# D1_Breakout_-_LCD_TH_Dupont_RJ45_Logo.net
KiCad netlist of a schematic drawn in EAGLE
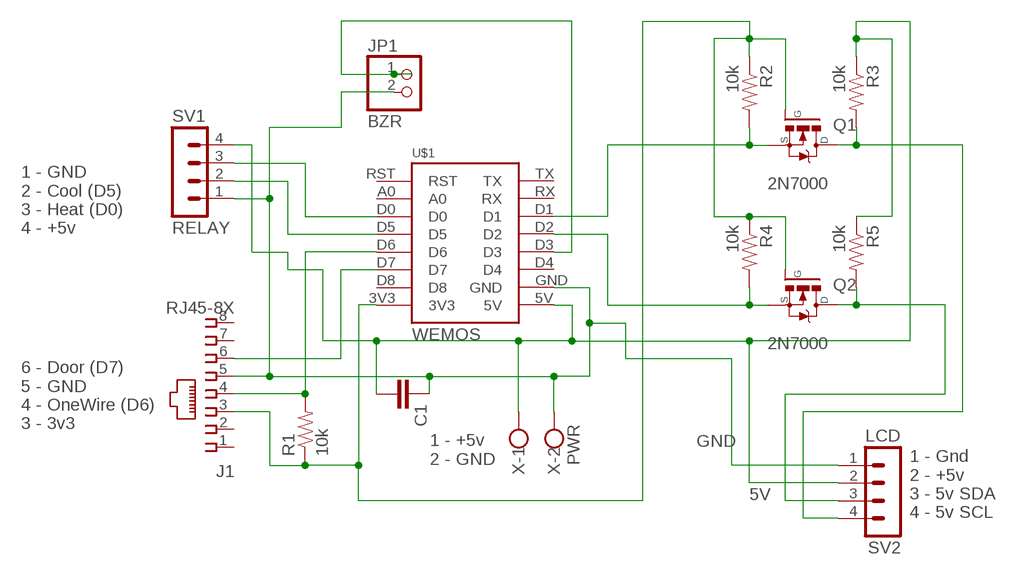
[diagram p0: schematic, sheet 1]

(export (version "E")
  (design (tool "Eeschema 10.0.6"))
  (components
    (comp (ref "C1")
      (value "100uF")
      (footprint "eagle-import:C5B3")
      (libsource (lib "eagle-import") (part "C5/3"))
    )
    (comp (ref "J1")
      (value "RJ45-8X")
      (footprint "eagle-import:RJ45-NO-SHIELD-NOLINE")
      (libsource (lib "eagle-import") (part "RJ45-8X"))
    )
    (comp (ref "JP1")
      (value "BZR")
      (footprint "eagle-import:1X02")
      (libsource (lib "eagle-import") (part "PINHD-1X2"))
    )
    (comp (ref "Q1")
      (value "2N7000")
      (footprint "eagle-import:TO-92")
      (libsource (lib "eagle-import") (part "2N7000"))
    )
    (comp (ref "Q2")
      (value "2N7000")
      (footprint "eagle-import:TO-92")
      (libsource (lib "eagle-import") (part "2N7000"))
    )
    (comp (ref "R1")
      (value "10k")
      (footprint "eagle-import:AXIAL-0.3")
      (libsource (lib "eagle-import") (part "10KOHM-HORIZ-1/4W-1%"))
    )
    (comp (ref "R2")
      (value "10k")
      (footprint "eagle-import:AXIAL-0.3")
      (libsource (lib "eagle-import") (part "10KOHM-HORIZ-1/4W-1%"))
    )
    (comp (ref "R3")
      (value "10k")
      (footprint "eagle-import:AXIAL-0.3")
      (libsource (lib "eagle-import") (part "10KOHM-HORIZ-1/4W-1%"))
    )
    (comp (ref "R4")
      (value "10k")
      (footprint "eagle-import:AXIAL-0.3")
      (libsource (lib "eagle-import") (part "10KOHM-HORIZ-1/4W-1%"))
    )
    (comp (ref "R5")
      (value "10k")
      (footprint "eagle-import:AXIAL-0.3")
      (libsource (lib "eagle-import") (part "10KOHM-HORIZ-1/4W-1%"))
    )
    (comp (ref "SV1")
      (value "RELAY")
      (footprint "eagle-import:MA04-1")
      (libsource (lib "eagle-import") (part "MA04-1"))
    )
    (comp (ref "SV2")
      (value "LCD")
      (footprint "eagle-import:MA04-1")
      (libsource (lib "eagle-import") (part "MA04-1"))
    )
    (comp (ref "U$1")
      (value "WEMOS")
      (footprint "eagle-import:WEMOS")
      (libsource (lib "eagle-import") (part "WEMOS"))
    )
    (comp (ref "X")
      (value "PWR")
      (footprint "eagle-import:W237-102")
      (fields (field (name "MPN") "237-102"))
      (libsource (lib "eagle-import") (part "W237-102"))
    )
  )
  (nets
    (net (code "1") (name "/5V") (class "Default")
      (node (ref "C1") (pin "2") (pinfunction "2_2") (pintype "passive"))
      (node (ref "R3") (pin "P$1") (pinfunction "1_P$1") (pintype "passive"))
      (node (ref "R5") (pin "P$1") (pinfunction "1_P$1") (pintype "passive"))
      (node (ref "SV1") (pin "4") (pinfunction "4_4") (pintype "passive"))
      (node (ref "SV2") (pin "2") (pinfunction "2_2") (pintype "passive"))
      (node (ref "U$1") (pin "5V") (pinfunction "5V_5V") (pintype "bidirectional"))
      (node (ref "X") (pin "1") (pinfunction "KL_1") (pintype "passive"))
    )
    (net (code "2") (name "/GND") (class "Default")
      (node (ref "C1") (pin "1") (pinfunction "1_1") (pintype "passive"))
      (node (ref "J1") (pin "5") (pinfunction "5_5") (pintype "passive"))
      (node (ref "JP1") (pin "2") (pinfunction "2_2") (pintype "passive"))
      (node (ref "SV1") (pin "1") (pinfunction "1_1") (pintype "passive"))
      (node (ref "SV2") (pin "1") (pinfunction "1_1") (pintype "passive"))
      (node (ref "U$1") (pin "GND") (pinfunction "GND_GND") (pintype "bidirectional"))
      (node (ref "X") (pin "2") (pinfunction "KL_2") (pintype "passive"))
    )
    (net (code "3") (name "Net-(J1-Pad6)") (class "Default")
      (node (ref "J1") (pin "6") (pinfunction "6_6") (pintype "passive"))
      (node (ref "U$1") (pin "D7") (pinfunction "D7_D7") (pintype "bidirectional"))
    )
    (net (code "4") (name "Net-(JP1-Pad1)") (class "Default")
      (node (ref "JP1") (pin "1") (pinfunction "1_1") (pintype "passive"))
      (node (ref "U$1") (pin "D3") (pinfunction "D3_D3") (pintype "bidirectional"))
    )
    (net (code "5") (name "Net-(Q1-D)") (class "Default")
      (node (ref "Q1") (pin "3") (pinfunction "D_3") (pintype "passive"))
      (node (ref "R3") (pin "P$2") (pinfunction "2_P$2") (pintype "passive"))
      (node (ref "SV2") (pin "4") (pinfunction "4_4") (pintype "passive"))
    )
    (net (code "6") (name "Net-(Q1-G)") (class "Default")
      (node (ref "J1") (pin "3") (pinfunction "3_3") (pintype "passive"))
      (node (ref "Q1") (pin "2") (pinfunction "G_2") (pintype "passive"))
      (node (ref "Q2") (pin "2") (pinfunction "G_2") (pintype "passive"))
      (node (ref "R1") (pin "P$1") (pinfunction "1_P$1") (pintype "passive"))
      (node (ref "R2") (pin "P$1") (pinfunction "1_P$1") (pintype "passive"))
      (node (ref "R4") (pin "P$1") (pinfunction "1_P$1") (pintype "passive"))
      (node (ref "U$1") (pin "3V3") (pinfunction "3V3_3V3") (pintype "bidirectional"))
    )
    (net (code "7") (name "Net-(Q1-S)") (class "Default")
      (node (ref "Q1") (pin "1") (pinfunction "S_1") (pintype "passive"))
      (node (ref "R2") (pin "P$2") (pinfunction "2_P$2") (pintype "passive"))
      (node (ref "U$1") (pin "D1") (pinfunction "D1_D1") (pintype "bidirectional"))
    )
    (net (code "8") (name "Net-(Q2-D)") (class "Default")
      (node (ref "Q2") (pin "3") (pinfunction "D_3") (pintype "passive"))
      (node (ref "R5") (pin "P$2") (pinfunction "2_P$2") (pintype "passive"))
      (node (ref "SV2") (pin "3") (pinfunction "3_3") (pintype "passive"))
    )
    (net (code "9") (name "Net-(Q2-S)") (class "Default")
      (node (ref "Q2") (pin "1") (pinfunction "S_1") (pintype "passive"))
      (node (ref "R4") (pin "P$2") (pinfunction "2_P$2") (pintype "passive"))
      (node (ref "U$1") (pin "D2") (pinfunction "D2_D2") (pintype "bidirectional"))
    )
    (net (code "10") (name "Net-(R1-2)") (class "Default")
      (node (ref "J1") (pin "4") (pinfunction "4_4") (pintype "passive"))
      (node (ref "R1") (pin "P$2") (pinfunction "2_P$2") (pintype "passive"))
      (node (ref "U$1") (pin "D6") (pinfunction "D6_D6") (pintype "bidirectional"))
    )
    (net (code "11") (name "Net-(SV1-Pad2)") (class "Default")
      (node (ref "SV1") (pin "2") (pinfunction "2_2") (pintype "passive"))
      (node (ref "U$1") (pin "D5") (pinfunction "D5_D5") (pintype "bidirectional"))
    )
    (net (code "12") (name "Net-(SV1-Pad3)") (class "Default")
      (node (ref "SV1") (pin "3") (pinfunction "3_3") (pintype "passive"))
      (node (ref "U$1") (pin "D0") (pinfunction "D0_D0") (pintype "bidirectional"))
    )
    (net (code "13") (name "unconnected-(J1-Pad1)") (class "Default")
      (node (ref "J1") (pin "1") (pinfunction "1_1") (pintype "passive"))
    )
    (net (code "14") (name "unconnected-(J1-Pad2)") (class "Default")
      (node (ref "J1") (pin "2") (pinfunction "2_2") (pintype "passive"))
    )
    (net (code "15") (name "unconnected-(J1-Pad7)") (class "Default")
      (node (ref "J1") (pin "7") (pinfunction "7_7") (pintype "passive"))
    )
    (net (code "16") (name "unconnected-(J1-Pad8)") (class "Default")
      (node (ref "J1") (pin "8") (pinfunction "8_8") (pintype "passive"))
    )
    (net (code "17") (name "unconnected-(U$1-PadA0)") (class "Default")
      (node (ref "U$1") (pin "A0") (pinfunction "A0_A0") (pintype "bidirectional"))
    )
    (net (code "18") (name "unconnected-(U$1-PadD4)") (class "Default")
      (node (ref "U$1") (pin "D4") (pinfunction "D4_D4") (pintype "bidirectional"))
    )
    (net (code "19") (name "unconnected-(U$1-PadD8)") (class "Default")
      (node (ref "U$1") (pin "D8") (pinfunction "D8_D8") (pintype "bidirectional"))
    )
    (net (code "20") (name "unconnected-(U$1-PadRST)") (class "Default")
      (node (ref "U$1") (pin "RST") (pinfunction "RST_RST") (pintype "bidirectional"))
    )
    (net (code "21") (name "unconnected-(U$1-PadRX)") (class "Default")
      (node (ref "U$1") (pin "RX") (pinfunction "RX_RX") (pintype "bidirectional"))
    )
    (net (code "22") (name "unconnected-(U$1-PadTX)") (class "Default")
      (node (ref "U$1") (pin "TX") (pinfunction "TX_TX") (pintype "bidirectional"))
    )
  )
)
